# mikroPAD.net
KiCad netlist of a schematic drawn in EAGLE
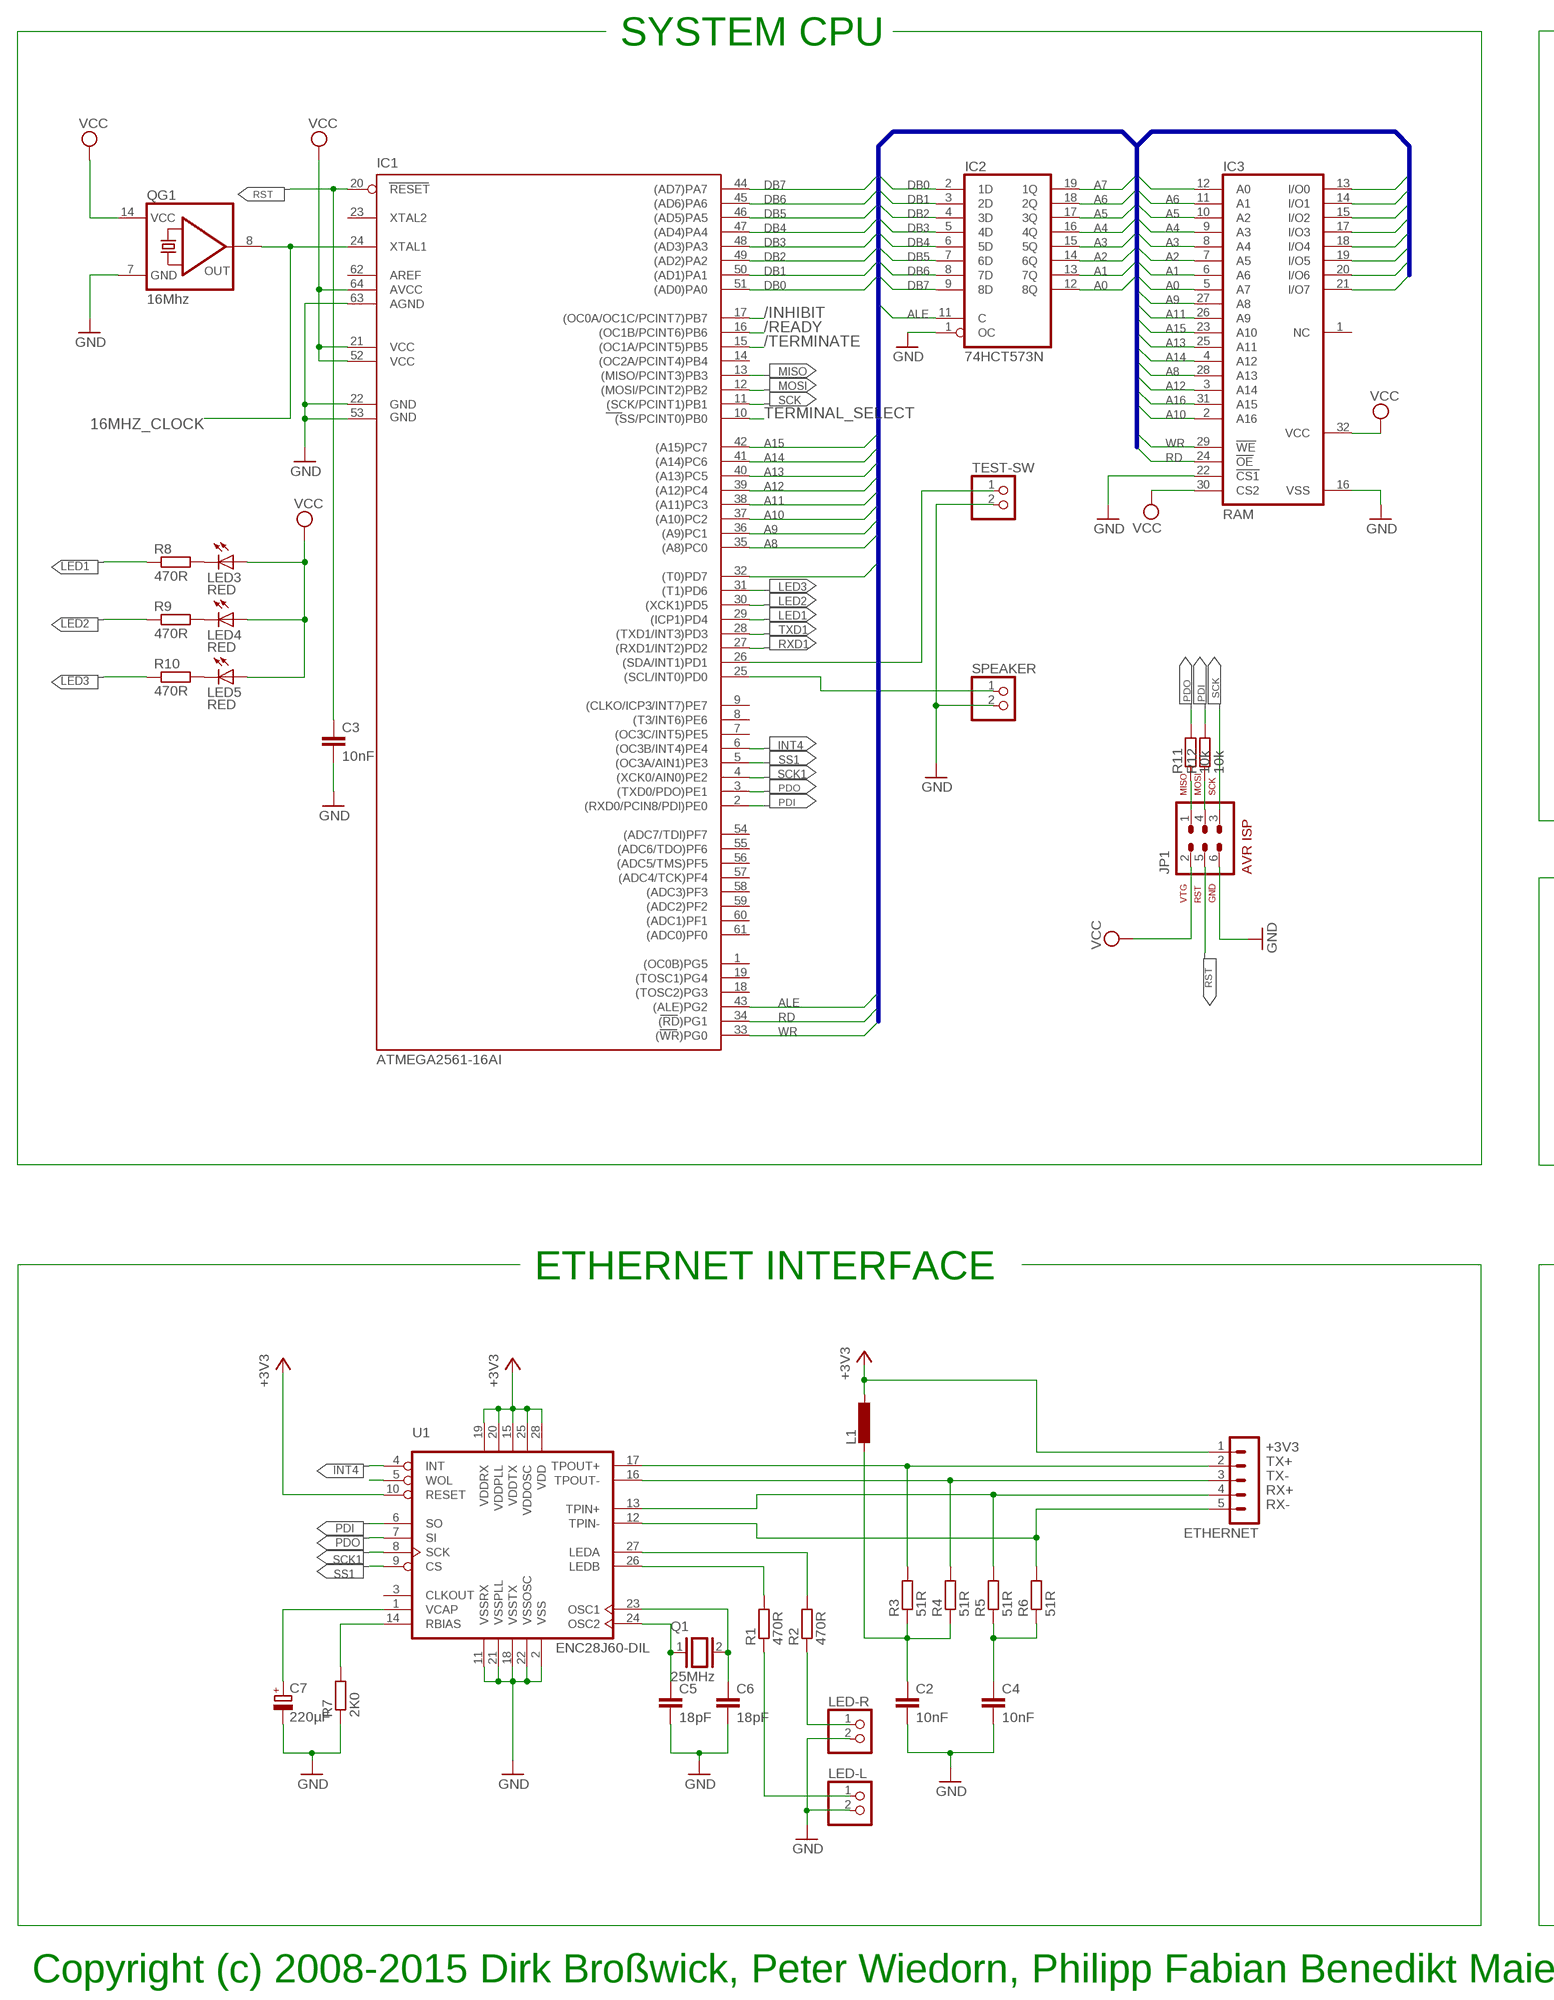
[diagram p0: schematic, sheet 1, part 1 of 2]
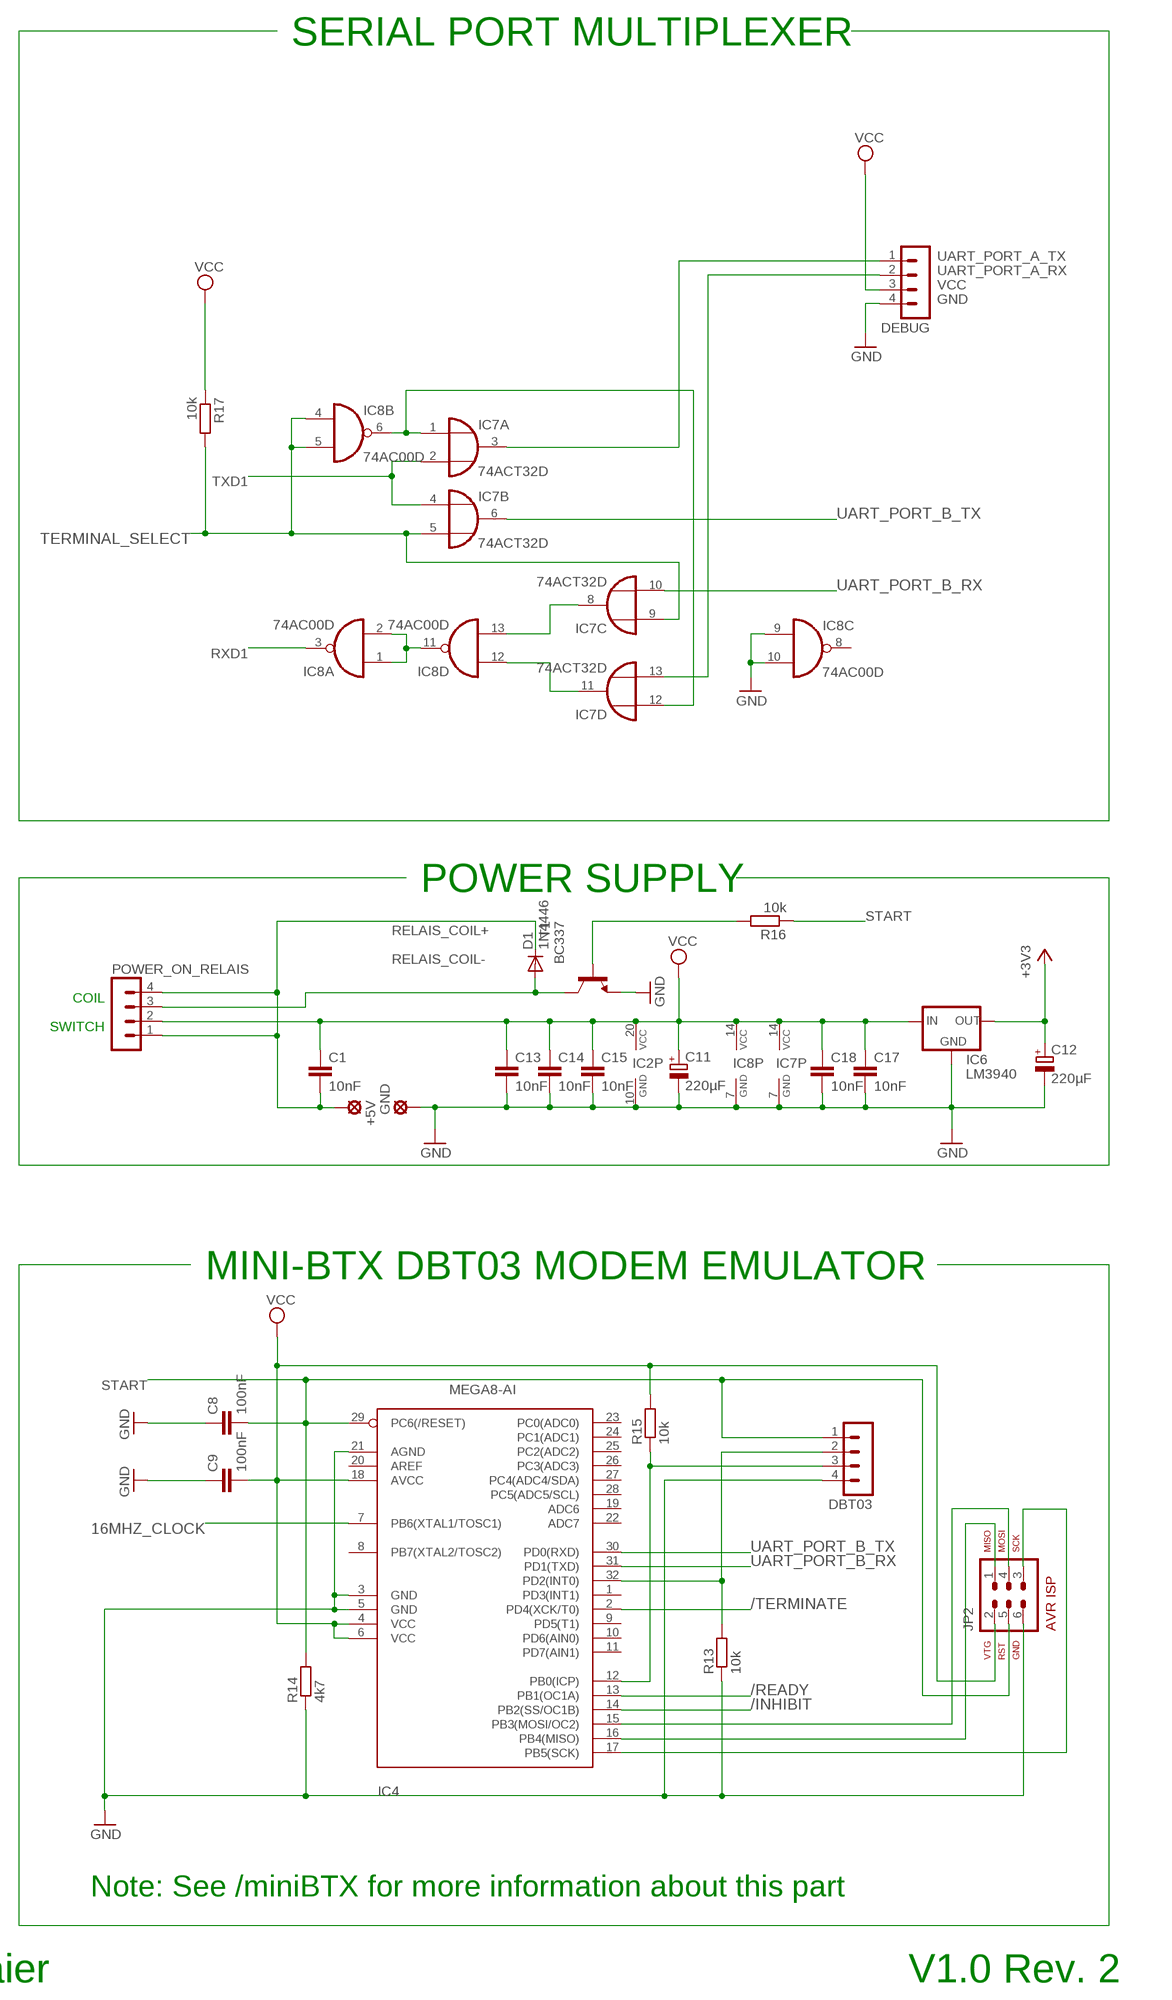
[diagram p1: schematic, sheet 1, part 2 of 2]

(export (version "E")
  (design (tool "Eeschema 10.0.6"))
  (components
    (comp (ref "+5V")
      (value "SE14")
      (footprint "eagle-import:SE14")
      (libsource (lib "eagle-import") (part "SE14"))
    )
    (comp (ref "C1")
      (value "10nF")
      (footprint "eagle-import:C025-025X050")
      (libsource (lib "eagle-import") (part "C-EU025-025X050"))
    )
    (comp (ref "C2")
      (value "10nF")
      (footprint "eagle-import:C025-030X050")
      (libsource (lib "eagle-import") (part "C-EU025-030X050"))
    )
    (comp (ref "C3")
      (value "10nF")
      (footprint "eagle-import:C025-025X050")
      (libsource (lib "eagle-import") (part "C-EU025-025X050"))
    )
    (comp (ref "C4")
      (value "10nF")
      (footprint "eagle-import:C025-030X050")
      (libsource (lib "eagle-import") (part "C-EU025-030X050"))
    )
    (comp (ref "C5")
      (value "18pF")
      (footprint "eagle-import:C025-025X050")
      (libsource (lib "eagle-import") (part "C-EU025-025X050"))
    )
    (comp (ref "C6")
      (value "18pF")
      (footprint "eagle-import:C025-025X050")
      (libsource (lib "eagle-import") (part "C-EU025-025X050"))
    )
    (comp (ref "C7")
      (value "220µF")
      (footprint "eagle-import:E2-5")
      (libsource (lib "eagle-import") (part "CPOL-EUE2-5"))
    )
    (comp (ref "C8")
      (value "100nF")
      (footprint "eagle-import:C025-025X050")
      (libsource (lib "eagle-import") (part "C-EU025-025X050"))
    )
    (comp (ref "C9")
      (value "100nF")
      (footprint "eagle-import:C025-025X050")
      (libsource (lib "eagle-import") (part "C-EU025-025X050"))
    )
    (comp (ref "C11")
      (value "220µF")
      (footprint "eagle-import:E2,5-7")
      (libsource (lib "eagle-import") (part "CPOL-EUE2.5-7"))
    )
    (comp (ref "C12")
      (value "220µF")
      (footprint "eagle-import:E2,5-7")
      (libsource (lib "eagle-import") (part "CPOL-EUE2.5-7"))
    )
    (comp (ref "C13")
      (value "10nF")
      (footprint "eagle-import:C025-025X050")
      (libsource (lib "eagle-import") (part "C-EU025-025X050"))
    )
    (comp (ref "C14")
      (value "10nF")
      (footprint "eagle-import:C025-025X050")
      (libsource (lib "eagle-import") (part "C-EU025-025X050"))
    )
    (comp (ref "C15")
      (value "10nF")
      (footprint "eagle-import:C025-025X050")
      (libsource (lib "eagle-import") (part "C-EU025-025X050"))
    )
    (comp (ref "C17")
      (value "10nF")
      (footprint "eagle-import:C025-025X050")
      (libsource (lib "eagle-import") (part "C-EU025-025X050"))
    )
    (comp (ref "C18")
      (value "10nF")
      (footprint "eagle-import:C025-025X050")
      (libsource (lib "eagle-import") (part "C-EU025-025X050"))
    )
    (comp (ref "D1")
      (value "1N4446")
      (footprint "eagle-import:DO35-10")
      (libsource (lib "eagle-import") (part "1N4446"))
    )
    (comp (ref "DBT03")
      (value "MA04-1")
      (footprint "eagle-import:MA04-1")
      (libsource (lib "eagle-import") (part "MA04-1"))
    )
    (comp (ref "DEBUG")
      (value "MA04-1")
      (footprint "eagle-import:MA04-1")
      (libsource (lib "eagle-import") (part "MA04-1"))
    )
    (comp (ref "ETHERNET")
      (value "MA05-1")
      (footprint "eagle-import:MA05-1")
      (libsource (lib "eagle-import") (part "MA05-1"))
    )
    (comp (ref "GND")
      (value "SE14")
      (footprint "eagle-import:SE14")
      (libsource (lib "eagle-import") (part "SE14"))
    )
    (comp (ref "IC1")
      (value "ATMEGA2561-16AI")
      (footprint "eagle-import:TQFP64")
      (libsource (lib "eagle-import") (part "ATMEGA1281AI-16"))
    )
    (comp (ref "IC2")
      (value "74HCT573N")
      (footprint "eagle-import:DIL20")
      (libsource (lib "eagle-import") (part "74573NHCT"))
    )
    (comp (ref "IC3")
      (value "RAM")
      (footprint "eagle-import:DIL32")
      (libsource (lib "eagle-import") (part "628128P"))
    )
    (comp (ref "IC4")
      (value "MEGA8-AI")
      (footprint "eagle-import:TQFP32-08")
      (libsource (lib "eagle-import") (part "MEGA8-AI"))
    )
    (comp (ref "IC6")
      (value "LM3940")
      (footprint "eagle-import:78XXS")
      (libsource (lib "eagle-import") (part "78XXS"))
    )
    (comp (ref "IC7")
      (value "74ACT32D")
      (footprint "eagle-import:SO14")
      (libsource (lib "eagle-import") (part "7432DACT"))
    )
    (comp (ref "IC8")
      (value "74AC00D")
      (footprint "eagle-import:SO14")
      (libsource (lib "eagle-import") (part "7400DAC"))
    )
    (comp (ref "JP1")
      (value "AVR-ISP-6")
      (footprint "eagle-import:AVR-ISP-6")
      (libsource (lib "eagle-import") (part "AVR-ISP-6"))
    )
    (comp (ref "JP2")
      (value "AVR-ISP-6")
      (footprint "eagle-import:AVR-ISP-6")
      (libsource (lib "eagle-import") (part "AVR-ISP-6"))
    )
    (comp (ref "L1")
      (value "L-EU0207/10")
      (footprint "eagle-import:0207_10")
      (libsource (lib "eagle-import") (part "L-EU0207/10"))
    )
    (comp (ref "LED-L")
      (value "PINHD-1X2")
      (footprint "eagle-import:1X02")
      (libsource (lib "eagle-import") (part "PINHD-1X2"))
    )
    (comp (ref "LED-R")
      (value "PINHD-1X2")
      (footprint "eagle-import:1X02")
      (libsource (lib "eagle-import") (part "PINHD-1X2"))
    )
    (comp (ref "LED3")
      (value "RED")
      (footprint "eagle-import:LED3MM")
      (libsource (lib "eagle-import") (part "LED3MM"))
    )
    (comp (ref "LED4")
      (value "RED")
      (footprint "eagle-import:LED3MM")
      (libsource (lib "eagle-import") (part "LED3MM"))
    )
    (comp (ref "LED5")
      (value "RED")
      (footprint "eagle-import:LED3MM")
      (libsource (lib "eagle-import") (part "LED3MM"))
    )
    (comp (ref "POWER_ON_RELAIS")
      (value "MA04-1")
      (footprint "eagle-import:MA04-1")
      (libsource (lib "eagle-import") (part "MA04-1"))
    )
    (comp (ref "Q1")
      (value "25MHz")
      (footprint "eagle-import:QS")
      (libsource (lib "eagle-import") (part "XTAL/S"))
    )
    (comp (ref "QG1")
      (value "16Mhz")
      (footprint "eagle-import:DIL14S")
      (libsource (lib "eagle-import") (part "QG5860"))
    )
    (comp (ref "R1")
      (value "470R")
      (footprint "eagle-import:0207_10")
      (libsource (lib "eagle-import") (part "R-EU_0207/10"))
    )
    (comp (ref "R2")
      (value "470R")
      (footprint "eagle-import:0207_10")
      (libsource (lib "eagle-import") (part "R-EU_0207/10"))
    )
    (comp (ref "R3")
      (value "51R")
      (footprint "eagle-import:0207_10")
      (libsource (lib "eagle-import") (part "R-EU_0207/10"))
    )
    (comp (ref "R4")
      (value "51R")
      (footprint "eagle-import:0207_10")
      (libsource (lib "eagle-import") (part "R-EU_0207/10"))
    )
    (comp (ref "R5")
      (value "51R")
      (footprint "eagle-import:0207_10")
      (libsource (lib "eagle-import") (part "R-EU_0207/10"))
    )
    (comp (ref "R6")
      (value "51R")
      (footprint "eagle-import:0207_10")
      (libsource (lib "eagle-import") (part "R-EU_0207/10"))
    )
    (comp (ref "R7")
      (value "2K0")
      (footprint "eagle-import:0207_10")
      (libsource (lib "eagle-import") (part "R-EU_0207/10"))
    )
    (comp (ref "R8")
      (value "470R")
      (footprint "eagle-import:0207_10")
      (libsource (lib "eagle-import") (part "R-EU_0207/10"))
    )
    (comp (ref "R9")
      (value "470R")
      (footprint "eagle-import:0207_10")
      (libsource (lib "eagle-import") (part "R-EU_0207/10"))
    )
    (comp (ref "R10")
      (value "470R")
      (footprint "eagle-import:0207_10")
      (libsource (lib "eagle-import") (part "R-EU_0207/10"))
    )
    (comp (ref "R11")
      (value "10k")
      (footprint "eagle-import:0204_5")
      (libsource (lib "eagle-import") (part "R-EU_0204/5"))
    )
    (comp (ref "R12")
      (value "10k")
      (footprint "eagle-import:0204_5")
      (libsource (lib "eagle-import") (part "R-EU_0204/5"))
    )
    (comp (ref "R13")
      (value "10k")
      (footprint "eagle-import:0204_5")
      (libsource (lib "eagle-import") (part "R-EU_0204/5"))
    )
    (comp (ref "R14")
      (value "4k7")
      (footprint "eagle-import:0204_5")
      (libsource (lib "eagle-import") (part "R-EU_0204/5"))
    )
    (comp (ref "R15")
      (value "10k")
      (footprint "eagle-import:0204_5")
      (libsource (lib "eagle-import") (part "R-EU_0204/5"))
    )
    (comp (ref "R16")
      (value "10k")
      (footprint "eagle-import:0207_12")
      (libsource (lib "eagle-import") (part "R-EU_0207/12"))
    )
    (comp (ref "R17")
      (value "10k")
      (footprint "eagle-import:0204_7")
      (libsource (lib "eagle-import") (part "R-EU_0204/7"))
    )
    (comp (ref "SPEAKER")
      (value "PINHD-1X2")
      (footprint "eagle-import:1X02")
      (libsource (lib "eagle-import") (part "PINHD-1X2"))
    )
    (comp (ref "T1")
      (value "BC337")
      (footprint "eagle-import:TO92")
      (libsource (lib "eagle-import") (part "BC337"))
    )
    (comp (ref "TEST-SW")
      (value "PINHD-1X2")
      (footprint "eagle-import:1X02")
      (libsource (lib "eagle-import") (part "PINHD-1X2"))
    )
    (comp (ref "U1")
      (value "ENC28J60-DIL")
      (footprint "eagle-import:DIL28-3")
      (libsource (lib "eagle-import") (part "ENC28J60-DIL"))
    )
  )
  (nets
    (net (code "1") (name "+3V3") (class "Default")
      (node (ref "C12") (pin "+") (pinfunction "+_+") (pintype "passive"))
      (node (ref "ETHERNET") (pin "1") (pinfunction "1_1") (pintype "passive"))
      (node (ref "IC6") (pin "OUT") (pinfunction "OUT_OUT") (pintype "passive"))
      (node (ref "L1") (pin "1") (pinfunction "1_1") (pintype "passive"))
      (node (ref "U1") (pin "10") (pinfunction "RESET_10") (pintype "input"))
      (node (ref "U1") (pin "15") (pinfunction "VDDTX_15") (pintype "power_in"))
      (node (ref "U1") (pin "19") (pinfunction "VDDRX_19") (pintype "power_in"))
      (node (ref "U1") (pin "20") (pinfunction "VDDPLL_20") (pintype "power_in"))
      (node (ref "U1") (pin "25") (pinfunction "VDDOSC_25") (pintype "power_in"))
      (node (ref "U1") (pin "28") (pinfunction "VDD_28") (pintype "power_in"))
    )
    (net (code "2") (name "/16MHZ_CLOCK") (class "Default")
      (node (ref "IC1") (pin "24") (pinfunction "XTAL1_24") (pintype "input"))
      (node (ref "IC4") (pin "7") (pinfunction "PB6(XTAL1/TOSC1)_7") (pintype "bidirectional"))
      (node (ref "QG1") (pin "8") (pinfunction "OUT_8") (pintype "output"))
    )
    (net (code "3") (name "/A0") (class "Default")
      (node (ref "IC2") (pin "12") (pinfunction "8Q_12") (pintype "tri_state"))
      (node (ref "IC3") (pin "5") (pinfunction "A7_5") (pintype "input"))
    )
    (net (code "4") (name "/A1") (class "Default")
      (node (ref "IC2") (pin "13") (pinfunction "7Q_13") (pintype "tri_state"))
      (node (ref "IC3") (pin "6") (pinfunction "A6_6") (pintype "input"))
    )
    (net (code "5") (name "/A2") (class "Default")
      (node (ref "IC2") (pin "14") (pinfunction "6Q_14") (pintype "tri_state"))
      (node (ref "IC3") (pin "7") (pinfunction "A5_7") (pintype "input"))
    )
    (net (code "6") (name "/A3") (class "Default")
      (node (ref "IC2") (pin "15") (pinfunction "5Q_15") (pintype "tri_state"))
      (node (ref "IC3") (pin "8") (pinfunction "A4_8") (pintype "input"))
    )
    (net (code "7") (name "/A4") (class "Default")
      (node (ref "IC2") (pin "16") (pinfunction "4Q_16") (pintype "tri_state"))
      (node (ref "IC3") (pin "9") (pinfunction "A3_9") (pintype "input"))
    )
    (net (code "8") (name "/A5") (class "Default")
      (node (ref "IC2") (pin "17") (pinfunction "3Q_17") (pintype "tri_state"))
      (node (ref "IC3") (pin "10") (pinfunction "A2_10") (pintype "input"))
    )
    (net (code "9") (name "/A6") (class "Default")
      (node (ref "IC2") (pin "18") (pinfunction "2Q_18") (pintype "tri_state"))
      (node (ref "IC3") (pin "11") (pinfunction "A1_11") (pintype "input"))
    )
    (net (code "10") (name "/A7") (class "Default")
      (node (ref "IC2") (pin "19") (pinfunction "1Q_19") (pintype "tri_state"))
      (node (ref "IC3") (pin "12") (pinfunction "A0_12") (pintype "input"))
    )
    (net (code "11") (name "/A8") (class "Default")
      (node (ref "IC1") (pin "35") (pinfunction "(A8)PC0_35") (pintype "bidirectional"))
      (node (ref "IC3") (pin "28") (pinfunction "A13_28") (pintype "input"))
    )
    (net (code "12") (name "/A9") (class "Default")
      (node (ref "IC1") (pin "36") (pinfunction "(A9)PC1_36") (pintype "bidirectional"))
      (node (ref "IC3") (pin "27") (pinfunction "A8_27") (pintype "input"))
    )
    (net (code "13") (name "/A10") (class "Default")
      (node (ref "IC1") (pin "37") (pinfunction "(A10)PC2_37") (pintype "bidirectional"))
      (node (ref "IC3") (pin "2") (pinfunction "A16_2") (pintype "input"))
    )
    (net (code "14") (name "/A11") (class "Default")
      (node (ref "IC1") (pin "38") (pinfunction "(A11)PC3_38") (pintype "bidirectional"))
      (node (ref "IC3") (pin "26") (pinfunction "A9_26") (pintype "input"))
    )
    (net (code "15") (name "/A12") (class "Default")
      (node (ref "IC1") (pin "39") (pinfunction "(A12)PC4_39") (pintype "bidirectional"))
      (node (ref "IC3") (pin "3") (pinfunction "A14_3") (pintype "input"))
    )
    (net (code "16") (name "/A13") (class "Default")
      (node (ref "IC1") (pin "40") (pinfunction "(A13)PC5_40") (pintype "bidirectional"))
      (node (ref "IC3") (pin "25") (pinfunction "A11_25") (pintype "input"))
    )
    (net (code "17") (name "/A14") (class "Default")
      (node (ref "IC1") (pin "41") (pinfunction "(A14)PC6_41") (pintype "bidirectional"))
      (node (ref "IC3") (pin "4") (pinfunction "A12_4") (pintype "input"))
    )
    (net (code "18") (name "/A15") (class "Default")
      (node (ref "IC1") (pin "42") (pinfunction "(A15)PC7_42") (pintype "bidirectional"))
      (node (ref "IC3") (pin "23") (pinfunction "A10_23") (pintype "input"))
    )
    (net (code "19") (name "/A16") (class "Default")
      (node (ref "IC1") (pin "32") (pinfunction "(T0)PD7_32") (pintype "bidirectional"))
      (node (ref "IC3") (pin "31") (pinfunction "A15_31") (pintype "input"))
    )
    (net (code "20") (name "/ALE") (class "Default")
      (node (ref "IC1") (pin "43") (pinfunction "(ALE)PG2_43") (pintype "bidirectional"))
      (node (ref "IC2") (pin "11") (pinfunction "C_11") (pintype "input"))
    )
    (net (code "21") (name "/DB0") (class "Default")
      (node (ref "IC1") (pin "51") (pinfunction "(AD0)PA0_51") (pintype "bidirectional"))
      (node (ref "IC2") (pin "2") (pinfunction "1D_2") (pintype "input"))
      (node (ref "IC3") (pin "15") (pinfunction "I/O2_15") (pintype "bidirectional"))
    )
    (net (code "22") (name "/DB1") (class "Default")
      (node (ref "IC1") (pin "50") (pinfunction "(AD1)PA1_50") (pintype "bidirectional"))
      (node (ref "IC2") (pin "3") (pinfunction "2D_3") (pintype "input"))
      (node (ref "IC3") (pin "14") (pinfunction "I/O1_14") (pintype "bidirectional"))
    )
    (net (code "23") (name "/DB2") (class "Default")
      (node (ref "IC1") (pin "49") (pinfunction "(AD2)PA2_49") (pintype "bidirectional"))
      (node (ref "IC2") (pin "4") (pinfunction "3D_4") (pintype "input"))
      (node (ref "IC3") (pin "13") (pinfunction "I/O0_13") (pintype "bidirectional"))
    )
    (net (code "24") (name "/DB3") (class "Default")
      (node (ref "IC1") (pin "48") (pinfunction "(AD3)PA3_48") (pintype "bidirectional"))
      (node (ref "IC2") (pin "5") (pinfunction "4D_5") (pintype "input"))
      (node (ref "IC3") (pin "17") (pinfunction "I/O3_17") (pintype "bidirectional"))
    )
    (net (code "25") (name "/DB4") (class "Default")
      (node (ref "IC1") (pin "47") (pinfunction "(AD4)PA4_47") (pintype "bidirectional"))
      (node (ref "IC2") (pin "6") (pinfunction "5D_6") (pintype "input"))
      (node (ref "IC3") (pin "18") (pinfunction "I/O4_18") (pintype "bidirectional"))
    )
    (net (code "26") (name "/DB5") (class "Default")
      (node (ref "IC1") (pin "46") (pinfunction "(AD5)PA5_46") (pintype "bidirectional"))
      (node (ref "IC2") (pin "7") (pinfunction "6D_7") (pintype "input"))
      (node (ref "IC3") (pin "19") (pinfunction "I/O5_19") (pintype "bidirectional"))
    )
    (net (code "27") (name "/DB6") (class "Default")
      (node (ref "IC1") (pin "45") (pinfunction "(AD6)PA6_45") (pintype "bidirectional"))
      (node (ref "IC2") (pin "8") (pinfunction "7D_8") (pintype "input"))
      (node (ref "IC3") (pin "20") (pinfunction "I/O6_20") (pintype "bidirectional"))
    )
    (net (code "28") (name "/DB7") (class "Default")
      (node (ref "IC1") (pin "44") (pinfunction "(AD7)PA7_44") (pintype "bidirectional"))
      (node (ref "IC2") (pin "9") (pinfunction "8D_9") (pintype "input"))
      (node (ref "IC3") (pin "21") (pinfunction "I/O7_21") (pintype "bidirectional"))
    )
    (net (code "29") (name "/INT4") (class "Default")
      (node (ref "IC1") (pin "6") (pinfunction "(OC3B/INT4)PE4_6") (pintype "bidirectional"))
      (node (ref "U1") (pin "4") (pinfunction "INT_4") (pintype "output"))
    )
    (net (code "30") (name "/LED1") (class "Default")
      (node (ref "IC1") (pin "29") (pinfunction "(ICP1)PD4_29") (pintype "bidirectional"))
      (node (ref "R8") (pin "1") (pinfunction "1_1") (pintype "passive"))
    )
    (net (code "31") (name "/LED2") (class "Default")
      (node (ref "IC1") (pin "30") (pinfunction "(XCK1)PD5_30") (pintype "bidirectional"))
      (node (ref "R9") (pin "1") (pinfunction "1_1") (pintype "passive"))
    )
    (net (code "32") (name "/LED3") (class "Default")
      (node (ref "IC1") (pin "31") (pinfunction "(T1)PD6_31") (pintype "bidirectional"))
      (node (ref "R10") (pin "1") (pinfunction "1_1") (pintype "passive"))
    )
    (net (code "33") (name "/MISO") (class "Default")
      (node (ref "IC1") (pin "13") (pinfunction "(MISO/PCINT3)PB3_13") (pintype "bidirectional"))
    )
    (net (code "34") (name "/MOSI") (class "Default")
      (node (ref "IC1") (pin "12") (pinfunction "(MOSI/PCINT2)PB2_12") (pintype "bidirectional"))
    )
    (net (code "35") (name "/PDI") (class "Default")
      (node (ref "IC1") (pin "2") (pinfunction "(RXD0/PCIN8/PDI)PE0_2") (pintype "bidirectional"))
      (node (ref "R12") (pin "2") (pinfunction "2_2") (pintype "passive"))
      (node (ref "U1") (pin "6") (pinfunction "SO_6") (pintype "output"))
    )
    (net (code "36") (name "/PDO") (class "Default")
      (node (ref "IC1") (pin "3") (pinfunction "(TXD0/PDO)PE1_3") (pintype "bidirectional"))
      (node (ref "R11") (pin "2") (pinfunction "2_2") (pintype "passive"))
      (node (ref "U1") (pin "7") (pinfunction "SI_7") (pintype "input"))
    )
    (net (code "37") (name "/RD") (class "Default")
      (node (ref "IC1") (pin "34") (pinfunction "(RD)PG1_34") (pintype "bidirectional"))
      (node (ref "IC3") (pin "24") (pinfunction "~{OE}_24") (pintype "input"))
    )
    (net (code "38") (name "/RELAIS_COIL+") (class "Default")
      (node (ref "+5V") (pin "MP") (pinfunction "MP_MP") (pintype "passive"))
      (node (ref "C1") (pin "2") (pinfunction "2_2") (pintype "passive"))
      (node (ref "D1") (pin "C") (pinfunction "C_C") (pintype "passive"))
      (node (ref "POWER_ON_RELAIS") (pin "1") (pinfunction "1_1") (pintype "passive"))
      (node (ref "POWER_ON_RELAIS") (pin "4") (pinfunction "4_4") (pintype "passive"))
    )
    (net (code "39") (name "/RELAIS_COIL-") (class "Default")
      (node (ref "D1") (pin "A") (pinfunction "A_A") (pintype "passive"))
      (node (ref "POWER_ON_RELAIS") (pin "3") (pinfunction "3_3") (pintype "passive"))
      (node (ref "T1") (pin "3") (pinfunction "C_3") (pintype "passive"))
    )
    (net (code "40") (name "/RST") (class "Default")
      (node (ref "C3") (pin "1") (pinfunction "1_1") (pintype "passive"))
      (node (ref "IC1") (pin "20") (pinfunction "RESET_20") (pintype "input"))
      (node (ref "JP1") (pin "5") (pinfunction "5_5") (pintype "passive"))
    )
    (net (code "41") (name "/RX+") (class "Default")
      (node (ref "ETHERNET") (pin "4") (pinfunction "4_4") (pintype "passive"))
      (node (ref "R5") (pin "2") (pinfunction "2_2") (pintype "passive"))
      (node (ref "U1") (pin "13") (pinfunction "TPIN+_13") (pintype "input"))
    )
    (net (code "42") (name "/RX-") (class "Default")
      (node (ref "ETHERNET") (pin "5") (pinfunction "5_5") (pintype "passive"))
      (node (ref "R6") (pin "2") (pinfunction "2_2") (pintype "passive"))
      (node (ref "U1") (pin "12") (pinfunction "TPIN-_12") (pintype "input"))
    )
    (net (code "43") (name "/RXD1") (class "Default")
      (node (ref "IC1") (pin "27") (pinfunction "(RXD1/INT2)PD2_27") (pintype "bidirectional"))
      (node (ref "IC8") (pin "3") (pinfunction "O_3") (pintype "output"))
    )
    (net (code "44") (name "/SCK") (class "Default")
      (node (ref "IC1") (pin "11") (pinfunction "(SCK/PCINT1)PB1_11") (pintype "bidirectional"))
      (node (ref "JP1") (pin "3") (pinfunction "3_3") (pintype "passive"))
    )
    (net (code "45") (name "/SCK1") (class "Default")
      (node (ref "IC1") (pin "4") (pinfunction "(XCK0/AIN0)PE2_4") (pintype "bidirectional"))
      (node (ref "U1") (pin "8") (pinfunction "SCK_8") (pintype "input"))
    )
    (net (code "46") (name "/SS1") (class "Default")
      (node (ref "IC1") (pin "5") (pinfunction "(OC3A/AIN1)PE3_5") (pintype "bidirectional"))
      (node (ref "U1") (pin "9") (pinfunction "CS_9") (pintype "input"))
    )
    (net (code "47") (name "/START") (class "Default")
      (node (ref "C8") (pin "2") (pinfunction "2_2") (pintype "passive"))
      (node (ref "DBT03") (pin "1") (pinfunction "1_1") (pintype "passive"))
      (node (ref "IC4") (pin "29") (pinfunction "PC6(/RESET)_29") (pintype "bidirectional"))
      (node (ref "JP2") (pin "5") (pinfunction "5_5") (pintype "passive"))
      (node (ref "R14") (pin "2") (pinfunction "2_2") (pintype "passive"))
      (node (ref "R16") (pin "1") (pinfunction "1_1") (pintype "passive"))
    )
    (net (code "48") (name "/TERMINAL_SELECT") (class "Default")
      (node (ref "IC1") (pin "10") (pinfunction "(SS/PCINT0)PB0_10") (pintype "bidirectional"))
      (node (ref "IC7") (pin "5") (pinfunction "I1_5") (pintype "input"))
      (node (ref "IC7") (pin "9") (pinfunction "I0_9") (pintype "input"))
      (node (ref "IC8") (pin "4") (pinfunction "I0_4") (pintype "input"))
      (node (ref "IC8") (pin "5") (pinfunction "I1_5") (pintype "input"))
      (node (ref "R17") (pin "2") (pinfunction "2_2") (pintype "passive"))
    )
    (net (code "49") (name "/TX+") (class "Default")
      (node (ref "ETHERNET") (pin "2") (pinfunction "2_2") (pintype "passive"))
      (node (ref "R3") (pin "2") (pinfunction "2_2") (pintype "passive"))
      (node (ref "U1") (pin "17") (pinfunction "TPOUT+_17") (pintype "output"))
    )
    (net (code "50") (name "/TX-") (class "Default")
      (node (ref "ETHERNET") (pin "3") (pinfunction "3_3") (pintype "passive"))
      (node (ref "R4") (pin "2") (pinfunction "2_2") (pintype "passive"))
      (node (ref "U1") (pin "16") (pinfunction "TPOUT-_16") (pintype "output"))
    )
    (net (code "51") (name "/TXD1") (class "Default")
      (node (ref "IC1") (pin "28") (pinfunction "(TXD1/INT3)PD3_28") (pintype "bidirectional"))
      (node (ref "IC7") (pin "2") (pinfunction "I1_2") (pintype "input"))
      (node (ref "IC7") (pin "4") (pinfunction "I0_4") (pintype "input"))
    )
    (net (code "52") (name "/UART_PORT_A_RX") (class "Default")
      (node (ref "DEBUG") (pin "2") (pinfunction "2_2") (pintype "passive"))
      (node (ref "IC7") (pin "13") (pinfunction "I1_13") (pintype "input"))
    )
    (net (code "53") (name "/UART_PORT_A_TX") (class "Default")
      (node (ref "DEBUG") (pin "1") (pinfunction "1_1") (pintype "passive"))
      (node (ref "IC7") (pin "3") (pinfunction "O_3") (pintype "output"))
    )
    (net (code "54") (name "/UART_PORT_B_RX") (class "Default")
      (node (ref "IC4") (pin "31") (pinfunction "PD1(TXD)_31") (pintype "bidirectional"))
      (node (ref "IC7") (pin "10") (pinfunction "I1_10") (pintype "input"))
    )
    (net (code "55") (name "/UART_PORT_B_TX") (class "Default")
      (node (ref "IC4") (pin "30") (pinfunction "PD0(RXD)_30") (pintype "bidirectional"))
      (node (ref "IC7") (pin "6") (pinfunction "O_6") (pintype "output"))
    )
    (net (code "56") (name "/WR") (class "Default")
      (node (ref "IC1") (pin "33") (pinfunction "(WR)PG0_33") (pintype "bidirectional"))
      (node (ref "IC3") (pin "29") (pinfunction "~{WE}_29") (pintype "input"))
    )
    (net (code "57") (name "/{slash}INHIBIT") (class "Default")
      (node (ref "IC1") (pin "17") (pinfunction "(OC0A/OC1C/PCINT7)PB7_17") (pintype "bidirectional"))
      (node (ref "IC4") (pin "14") (pinfunction "PB2(SS/OC1B)_14") (pintype "bidirectional"))
    )
    (net (code "58") (name "/{slash}READY") (class "Default")
      (node (ref "IC1") (pin "16") (pinfunction "(OC1B/PCINT6)PB6_16") (pintype "bidirectional"))
      (node (ref "IC4") (pin "13") (pinfunction "PB1(OC1A)_13") (pintype "bidirectional"))
    )
    (net (code "59") (name "/{slash}TERMINATE") (class "Default")
      (node (ref "IC1") (pin "15") (pinfunction "(OC1A/PCINT5)PB5_15") (pintype "bidirectional"))
      (node (ref "IC4") (pin "2") (pinfunction "PD4(XCK/T0)_2") (pintype "bidirectional"))
    )
    (net (code "60") (name "GND") (class "Default")
      (node (ref "C11") (pin "-") (pinfunction "-_-") (pintype "passive"))
      (node (ref "C12") (pin "-") (pinfunction "-_-") (pintype "passive"))
      (node (ref "C13") (pin "2") (pinfunction "2_2") (pintype "passive"))
      (node (ref "C14") (pin "2") (pinfunction "2_2") (pintype "passive"))
      (node (ref "C15") (pin "2") (pinfunction "2_2") (pintype "passive"))
      (node (ref "C17") (pin "2") (pinfunction "2_2") (pintype "passive"))
      (node (ref "C18") (pin "2") (pinfunction "2_2") (pintype "passive"))
      (node (ref "C2") (pin "2") (pinfunction "2_2") (pintype "passive"))
      (node (ref "C3") (pin "2") (pinfunction "2_2") (pintype "passive"))
      (node (ref "C4") (pin "2") (pinfunction "2_2") (pintype "passive"))
      (node (ref "C5") (pin "2") (pinfunction "2_2") (pintype "passive"))
      (node (ref "C6") (pin "2") (pinfunction "2_2") (pintype "passive"))
      (node (ref "C7") (pin "-") (pinfunction "-_-") (pintype "passive"))
      (node (ref "C8") (pin "1") (pinfunction "1_1") (pintype "passive"))
      (node (ref "C9") (pin "1") (pinfunction "1_1") (pintype "passive"))
      (node (ref "DBT03") (pin "4") (pinfunction "4_4") (pintype "passive"))
      (node (ref "DEBUG") (pin "4") (pinfunction "4_4") (pintype "passive"))
      (node (ref "GND") (pin "MP") (pinfunction "MP_MP") (pintype "passive"))
      (node (ref "IC1") (pin "22") (pinfunction "GND_22") (pintype "power_in"))
      (node (ref "IC1") (pin "53") (pinfunction "GND1_53") (pintype "power_in"))
      (node (ref "IC1") (pin "63") (pinfunction "AGND_63") (pintype "power_in"))
      (node (ref "IC2") (pin "1") (pinfunction "OC_1") (pintype "input"))
      (node (ref "IC2") (pin "10") (pinfunction "GND_10") (pintype "power_in"))
      (node (ref "IC3") (pin "16") (pinfunction "VSS_16") (pintype "power_in"))
      (node (ref "IC3") (pin "22") (pinfunction "~{CS1}_22") (pintype "input"))
      (node (ref "IC4") (pin "21") (pinfunction "AGND_21") (pintype "power_in"))
      (node (ref "IC4") (pin "3") (pinfunction "GND_3") (pintype "power_in"))
      (node (ref "IC4") (pin "5") (pinfunction "GND_5") (pintype "power_in"))
      (node (ref "IC6") (pin "GND") (pinfunction "GND_GND") (pintype "input"))
      (node (ref "IC7") (pin "7") (pinfunction "GND_7") (pintype "power_in"))
      (node (ref "IC8") (pin "10") (pinfunction "I1_10") (pintype "input"))
      (node (ref "IC8") (pin "7") (pinfunction "GND_7") (pintype "power_in"))
      (node (ref "IC8") (pin "9") (pinfunction "I0_9") (pintype "input"))
      (node (ref "JP1") (pin "6") (pinfunction "6_6") (pintype "passive"))
      (node (ref "JP2") (pin "6") (pinfunction "6_6") (pintype "passive"))
      (node (ref "LED-L") (pin "2") (pinfunction "2_2") (pintype "passive"))
      (node (ref "LED-R") (pin "2") (pinfunction "2_2") (pintype "passive"))
      (node (ref "QG1") (pin "7") (pinfunction "GND_7") (pintype "power_in"))
      (node (ref "R13") (pin "1") (pinfunction "1_1") (pintype "passive"))
      (node (ref "R14") (pin "1") (pinfunction "1_1") (pintype "passive"))
      (node (ref "R7") (pin "1") (pinfunction "1_1") (pintype "passive"))
      (node (ref "SPEAKER") (pin "2") (pinfunction "2_2") (pintype "passive"))
      (node (ref "T1") (pin "1") (pinfunction "E_1") (pintype "passive"))
      (node (ref "TEST-SW") (pin "2") (pinfunction "2_2") (pintype "passive"))
      (node (ref "U1") (pin "11") (pinfunction "VSSRX_11") (pintype "power_in"))
      (node (ref "U1") (pin "18") (pinfunction "VSSTX_18") (pintype "power_in"))
      (node (ref "U1") (pin "2") (pinfunction "VSS_2") (pintype "power_in"))
      (node (ref "U1") (pin "21") (pinfunction "VSSPLL_21") (pintype "power_in"))
      (node (ref "U1") (pin "22") (pinfunction "VSSOSC_22") (pintype "power_in"))
    )
    (net (code "61") (name "Net-(C2-Pad1)") (class "Default")
      (node (ref "C2") (pin "1") (pinfunction "1_1") (pintype "passive"))
      (node (ref "L1") (pin "2") (pinfunction "2_2") (pintype "passive"))
      (node (ref "R3") (pin "1") (pinfunction "1_1") (pintype "passive"))
      (node (ref "R4") (pin "1") (pinfunction "1_1") (pintype "passive"))
    )
    (net (code "62") (name "Net-(C4-Pad1)") (class "Default")
      (node (ref "C4") (pin "1") (pinfunction "1_1") (pintype "passive"))
      (node (ref "R5") (pin "1") (pinfunction "1_1") (pintype "passive"))
      (node (ref "R6") (pin "1") (pinfunction "1_1") (pintype "passive"))
    )
    (net (code "63") (name "Net-(IC1-(SCL{slash}INT0)PD0)") (class "Default")
      (node (ref "IC1") (pin "25") (pinfunction "(SCL/INT0)PD0_25") (pintype "bidirectional"))
      (node (ref "SPEAKER") (pin "1") (pinfunction "1_1") (pintype "passive"))
    )
    (net (code "64") (name "Net-(IC1-(SDA{slash}INT1)PD1)") (class "Default")
      (node (ref "IC1") (pin "26") (pinfunction "(SDA/INT1)PD1_26") (pintype "bidirectional"))
      (node (ref "TEST-SW") (pin "1") (pinfunction "1_1") (pintype "passive"))
    )
    (net (code "65") (name "Net-(IC4-PB0(ICP))") (class "Default")
      (node (ref "DBT03") (pin "3") (pinfunction "3_3") (pintype "passive"))
      (node (ref "IC4") (pin "12") (pinfunction "PB0(ICP)_12") (pintype "bidirectional"))
      (node (ref "R15") (pin "1") (pinfunction "1_1") (pintype "passive"))
    )
    (net (code "66") (name "Net-(IC4-PB3(MOSI{slash}OC2))") (class "Default")
      (node (ref "IC4") (pin "15") (pinfunction "PB3(MOSI/OC2)_15") (pintype "bidirectional"))
      (node (ref "JP2") (pin "4") (pinfunction "4_4") (pintype "passive"))
    )
    (net (code "67") (name "Net-(IC4-PB4(MISO))") (class "Default")
      (node (ref "IC4") (pin "16") (pinfunction "PB4(MISO)_16") (pintype "bidirectional"))
      (node (ref "JP2") (pin "1") (pinfunction "1_1") (pintype "passive"))
    )
    (net (code "68") (name "Net-(IC4-PB5(SCK))") (class "Default")
      (node (ref "IC4") (pin "17") (pinfunction "PB5(SCK)_17") (pintype "bidirectional"))
      (node (ref "JP2") (pin "3") (pinfunction "3_3") (pintype "passive"))
    )
    (net (code "69") (name "Net-(IC4-PD2(INT0))") (class "Default")
      (node (ref "DBT03") (pin "2") (pinfunction "2_2") (pintype "passive"))
      (node (ref "IC4") (pin "32") (pinfunction "PD2(INT0)_32") (pintype "bidirectional"))
      (node (ref "R13") (pin "2") (pinfunction "2_2") (pintype "passive"))
    )
    (net (code "70") (name "Net-(IC7A-I0)") (class "Default")
      (node (ref "IC7") (pin "1") (pinfunction "I0_1") (pintype "input"))
      (node (ref "IC7") (pin "12") (pinfunction "I0_12") (pintype "input"))
      (node (ref "IC8") (pin "6") (pinfunction "O_6") (pintype "output"))
    )
    (net (code "71") (name "Net-(IC7C-O)") (class "Default")
      (node (ref "IC7") (pin "8") (pinfunction "O_8") (pintype "output"))
      (node (ref "IC8") (pin "13") (pinfunction "I1_13") (pintype "input"))
    )
    (net (code "72") (name "Net-(IC7D-O)") (class "Default")
      (node (ref "IC7") (pin "11") (pinfunction "O_11") (pintype "output"))
      (node (ref "IC8") (pin "12") (pinfunction "I0_12") (pintype "input"))
    )
    (net (code "73") (name "Net-(IC8A-I0)") (class "Default")
      (node (ref "IC8") (pin "1") (pinfunction "I0_1") (pintype "input"))
      (node (ref "IC8") (pin "11") (pinfunction "O_11") (pintype "output"))
      (node (ref "IC8") (pin "2") (pinfunction "I1_2") (pintype "input"))
    )
    (net (code "74") (name "Net-(JP1-Pad1)") (class "Default")
      (node (ref "JP1") (pin "1") (pinfunction "1_1") (pintype "passive"))
      (node (ref "R11") (pin "1") (pinfunction "1_1") (pintype "passive"))
    )
    (net (code "75") (name "Net-(JP1-Pad4)") (class "Default")
      (node (ref "JP1") (pin "4") (pinfunction "4_4") (pintype "passive"))
      (node (ref "R12") (pin "1") (pinfunction "1_1") (pintype "passive"))
    )
    (net (code "76") (name "Net-(LED-L-Pad1)") (class "Default")
      (node (ref "LED-L") (pin "1") (pinfunction "1_1") (pintype "passive"))
      (node (ref "R1") (pin "1") (pinfunction "1_1") (pintype "passive"))
    )
    (net (code "77") (name "Net-(LED-R-Pad1)") (class "Default")
      (node (ref "LED-R") (pin "1") (pinfunction "1_1") (pintype "passive"))
      (node (ref "R2") (pin "1") (pinfunction "1_1") (pintype "passive"))
    )
    (net (code "78") (name "Net-(LED3-C)") (class "Default")
      (node (ref "LED3") (pin "K") (pinfunction "C_K") (pintype "passive"))
      (node (ref "R8") (pin "2") (pinfunction "2_2") (pintype "passive"))
    )
    (net (code "79") (name "Net-(LED4-C)") (class "Default")
      (node (ref "LED4") (pin "K") (pinfunction "C_K") (pintype "passive"))
      (node (ref "R9") (pin "2") (pinfunction "2_2") (pintype "passive"))
    )
    (net (code "80") (name "Net-(LED5-C)") (class "Default")
      (node (ref "LED5") (pin "K") (pinfunction "C_K") (pintype "passive"))
      (node (ref "R10") (pin "2") (pinfunction "2_2") (pintype "passive"))
    )
    (net (code "81") (name "Net-(T1-B)") (class "Default")
      (node (ref "R16") (pin "2") (pinfunction "2_2") (pintype "passive"))
      (node (ref "T1") (pin "2") (pinfunction "B_2") (pintype "passive"))
    )
    (net (code "82") (name "Net-(U1-LEDA)") (class "Default")
      (node (ref "R2") (pin "2") (pinfunction "2_2") (pintype "passive"))
      (node (ref "U1") (pin "27") (pinfunction "LEDA_27") (pintype "output"))
    )
    (net (code "83") (name "Net-(U1-LEDB)") (class "Default")
      (node (ref "R1") (pin "2") (pinfunction "2_2") (pintype "passive"))
      (node (ref "U1") (pin "26") (pinfunction "LEDB_26") (pintype "output"))
    )
    (net (code "84") (name "Net-(U1-OSC1)") (class "Default")
      (node (ref "C6") (pin "1") (pinfunction "1_1") (pintype "passive"))
      (node (ref "Q1") (pin "2") (pinfunction "2_2") (pintype "passive"))
      (node (ref "U1") (pin "23") (pinfunction "OSC1_23") (pintype "input"))
    )
    (net (code "85") (name "Net-(U1-OSC2)") (class "Default")
      (node (ref "C5") (pin "1") (pinfunction "1_1") (pintype "passive"))
      (node (ref "Q1") (pin "1") (pinfunction "1_1") (pintype "passive"))
      (node (ref "U1") (pin "24") (pinfunction "OSC2_24") (pintype "output"))
    )
    (net (code "86") (name "Net-(U1-RBIAS)") (class "Default")
      (node (ref "R7") (pin "2") (pinfunction "2_2") (pintype "passive"))
      (node (ref "U1") (pin "14") (pinfunction "RBIAS_14") (pintype "passive"))
    )
    (net (code "87") (name "Net-(U1-VCAP)") (class "Default")
      (node (ref "C7") (pin "+") (pinfunction "+_+") (pintype "passive"))
      (node (ref "U1") (pin "1") (pinfunction "VCAP_1") (pintype "power_in"))
    )
    (net (code "88") (name "VCC") (class "Default")
      (node (ref "C1") (pin "1") (pinfunction "1_1") (pintype "passive"))
      (node (ref "C11") (pin "+") (pinfunction "+_+") (pintype "passive"))
      (node (ref "C13") (pin "1") (pinfunction "1_1") (pintype "passive"))
      (node (ref "C14") (pin "1") (pinfunction "1_1") (pintype "passive"))
      (node (ref "C15") (pin "1") (pinfunction "1_1") (pintype "passive"))
      (node (ref "C17") (pin "1") (pinfunction "1_1") (pintype "passive"))
      (node (ref "C18") (pin "1") (pinfunction "1_1") (pintype "passive"))
      (node (ref "C9") (pin "2") (pinfunction "2_2") (pintype "passive"))
      (node (ref "DEBUG") (pin "3") (pinfunction "3_3") (pintype "passive"))
      (node (ref "IC1") (pin "21") (pinfunction "VCC_21") (pintype "power_in"))
      (node (ref "IC1") (pin "52") (pinfunction "VCC1_52") (pintype "power_in"))
      (node (ref "IC1") (pin "64") (pinfunction "AVCC_64") (pintype "power_in"))
      (node (ref "IC2") (pin "20") (pinfunction "VCC_20") (pintype "power_in"))
      (node (ref "IC3") (pin "30") (pinfunction "CS2_30") (pintype "input"))
      (node (ref "IC3") (pin "32") (pinfunction "VCC_32") (pintype "power_in"))
      (node (ref "IC4") (pin "18") (pinfunction "AVCC_18") (pintype "power_in"))
      (node (ref "IC4") (pin "4") (pinfunction "VCC_4") (pintype "power_in"))
      (node (ref "IC4") (pin "6") (pinfunction "VCC_6") (pintype "power_in"))
      (node (ref "IC6") (pin "IN") (pinfunction "IN_IN") (pintype "input"))
      (node (ref "IC7") (pin "14") (pinfunction "VCC_14") (pintype "power_in"))
      (node (ref "IC8") (pin "14") (pinfunction "VCC_14") (pintype "power_in"))
      (node (ref "JP1") (pin "2") (pinfunction "2_2") (pintype "passive"))
      (node (ref "JP2") (pin "2") (pinfunction "2_2") (pintype "passive"))
      (node (ref "LED3") (pin "A") (pinfunction "A_A") (pintype "passive"))
      (node (ref "LED4") (pin "A") (pinfunction "A_A") (pintype "passive"))
      (node (ref "LED5") (pin "A") (pinfunction "A_A") (pintype "passive"))
      (node (ref "POWER_ON_RELAIS") (pin "2") (pinfunction "2_2") (pintype "passive"))
      (node (ref "QG1") (pin "14") (pinfunction "VCC_14") (pintype "power_in"))
      (node (ref "R15") (pin "2") (pinfunction "2_2") (pintype "passive"))
      (node (ref "R17") (pin "1") (pinfunction "1_1") (pintype "passive"))
    )
    (net (code "89") (name "unconnected-(IC1-(ADC0)PF0-Pad61)") (class "Default")
      (node (ref "IC1") (pin "61") (pinfunction "(ADC0)PF0_61") (pintype "bidirectional"))
    )
    (net (code "90") (name "unconnected-(IC1-(ADC1)PF1-Pad60)") (class "Default")
      (node (ref "IC1") (pin "60") (pinfunction "(ADC1)PF1_60") (pintype "bidirectional"))
    )
    (net (code "91") (name "unconnected-(IC1-(ADC2)PF2-Pad59)") (class "Default")
      (node (ref "IC1") (pin "59") (pinfunction "(ADC2)PF2_59") (pintype "bidirectional"))
    )
    (net (code "92") (name "unconnected-(IC1-(ADC3)PF3-Pad58)") (class "Default")
      (node (ref "IC1") (pin "58") (pinfunction "(ADC3)PF3_58") (pintype "bidirectional"))
    )
    (net (code "93") (name "unconnected-(IC1-(ADC4{slash}TCK)PF4-Pad57)") (class "Default")
      (node (ref "IC1") (pin "57") (pinfunction "(ADC4/TCK)PF4_57") (pintype "bidirectional"))
    )
    (net (code "94") (name "unconnected-(IC1-(ADC5{slash}TMS)PF5-Pad56)") (class "Default")
      (node (ref "IC1") (pin "56") (pinfunction "(ADC5/TMS)PF5_56") (pintype "bidirectional"))
    )
    (net (code "95") (name "unconnected-(IC1-(ADC6{slash}TDO)PF6-Pad55)") (class "Default")
      (node (ref "IC1") (pin "55") (pinfunction "(ADC6/TDO)PF6_55") (pintype "bidirectional"))
    )
    (net (code "96") (name "unconnected-(IC1-(ADC7{slash}TDI)PF7-Pad54)") (class "Default")
      (node (ref "IC1") (pin "54") (pinfunction "(ADC7/TDI)PF7_54") (pintype "bidirectional"))
    )
    (net (code "97") (name "unconnected-(IC1-(CLKO{slash}ICP3{slash}INT7)PE7-Pad9)") (class "Default")
      (node (ref "IC1") (pin "9") (pinfunction "(CLKO/ICP3/INT7)PE7_9") (pintype "bidirectional"))
    )
    (net (code "98") (name "unconnected-(IC1-(OC0B)PG5-Pad1)") (class "Default")
      (node (ref "IC1") (pin "1") (pinfunction "(OC0B)PG5_1") (pintype "bidirectional"))
    )
    (net (code "99") (name "unconnected-(IC1-(OC2A{slash}PCINT4)PB4-Pad14)") (class "Default")
      (node (ref "IC1") (pin "14") (pinfunction "(OC2A/PCINT4)PB4_14") (pintype "bidirectional"))
    )
    (net (code "100") (name "unconnected-(IC1-(OC3C{slash}INT5)PE5-Pad7)") (class "Default")
      (node (ref "IC1") (pin "7") (pinfunction "(OC3C/INT5)PE5_7") (pintype "bidirectional"))
    )
    (net (code "101") (name "unconnected-(IC1-(T3{slash}INT6)PE6-Pad8)") (class "Default")
      (node (ref "IC1") (pin "8") (pinfunction "(T3/INT6)PE6_8") (pintype "bidirectional"))
    )
    (net (code "102") (name "unconnected-(IC1-(TOSC1)PG4-Pad19)") (class "Default")
      (node (ref "IC1") (pin "19") (pinfunction "(TOSC1)PG4_19") (pintype "bidirectional"))
    )
    (net (code "103") (name "unconnected-(IC1-(TOSC2)PG3-Pad18)") (class "Default")
      (node (ref "IC1") (pin "18") (pinfunction "(TOSC2)PG3_18") (pintype "bidirectional"))
    )
    (net (code "104") (name "unconnected-(IC1-AREF-Pad62)") (class "Default")
      (node (ref "IC1") (pin "62") (pinfunction "AREF_62") (pintype "bidirectional"))
    )
    (net (code "105") (name "unconnected-(IC1-XTAL2-Pad23)") (class "Default")
      (node (ref "IC1") (pin "23") (pinfunction "XTAL2_23") (pintype "output"))
    )
    (net (code "106") (name "unconnected-(IC3-NC-Pad1)") (class "Default")
      (node (ref "IC3") (pin "1") (pinfunction "NC_1") (pintype "no_connect"))
    )
    (net (code "107") (name "unconnected-(IC4-ADC6-Pad19)") (class "Default")
      (node (ref "IC4") (pin "19") (pinfunction "ADC6_19") (pintype "bidirectional"))
    )
    (net (code "108") (name "unconnected-(IC4-ADC7-Pad22)") (class "Default")
      (node (ref "IC4") (pin "22") (pinfunction "ADC7_22") (pintype "bidirectional"))
    )
    (net (code "109") (name "unconnected-(IC4-AREF-Pad20)") (class "Default")
      (node (ref "IC4") (pin "20") (pinfunction "AREF_20") (pintype "passive"))
    )
    (net (code "110") (name "unconnected-(IC4-PB7(XTAL2{slash}TOSC2)-Pad8)") (class "Default")
      (node (ref "IC4") (pin "8") (pinfunction "PB7(XTAL2/TOSC2)_8") (pintype "bidirectional"))
    )
    (net (code "111") (name "unconnected-(IC4-PC0(ADC0)-Pad23)") (class "Default")
      (node (ref "IC4") (pin "23") (pinfunction "PC0(ADC0)_23") (pintype "bidirectional"))
    )
    (net (code "112") (name "unconnected-(IC4-PC1(ADC1)-Pad24)") (class "Default")
      (node (ref "IC4") (pin "24") (pinfunction "PC1(ADC1)_24") (pintype "bidirectional"))
    )
    (net (code "113") (name "unconnected-(IC4-PC2(ADC2)-Pad25)") (class "Default")
      (node (ref "IC4") (pin "25") (pinfunction "PC2(ADC2)_25") (pintype "bidirectional"))
    )
    (net (code "114") (name "unconnected-(IC4-PC3(ADC3)-Pad26)") (class "Default")
      (node (ref "IC4") (pin "26") (pinfunction "PC3(ADC3)_26") (pintype "bidirectional"))
    )
    (net (code "115") (name "unconnected-(IC4-PC4(ADC4{slash}SDA)-Pad27)") (class "Default")
      (node (ref "IC4") (pin "27") (pinfunction "PC4(ADC4/SDA)_27") (pintype "bidirectional"))
    )
    (net (code "116") (name "unconnected-(IC4-PC5(ADC5{slash}SCL)-Pad28)") (class "Default")
      (node (ref "IC4") (pin "28") (pinfunction "PC5(ADC5/SCL)_28") (pintype "bidirectional"))
    )
    (net (code "117") (name "unconnected-(IC4-PD3(INT1)-Pad1)") (class "Default")
      (node (ref "IC4") (pin "1") (pinfunction "PD3(INT1)_1") (pintype "bidirectional"))
    )
    (net (code "118") (name "unconnected-(IC4-PD5(T1)-Pad9)") (class "Default")
      (node (ref "IC4") (pin "9") (pinfunction "PD5(T1)_9") (pintype "bidirectional"))
    )
    (net (code "119") (name "unconnected-(IC4-PD6(AIN0)-Pad10)") (class "Default")
      (node (ref "IC4") (pin "10") (pinfunction "PD6(AIN0)_10") (pintype "bidirectional"))
    )
    (net (code "120") (name "unconnected-(IC4-PD7(AIN1)-Pad11)") (class "Default")
      (node (ref "IC4") (pin "11") (pinfunction "PD7(AIN1)_11") (pintype "bidirectional"))
    )
    (net (code "121") (name "unconnected-(IC8C-O-Pad8)") (class "Default")
      (node (ref "IC8") (pin "8") (pinfunction "O_8") (pintype "output"))
    )
    (net (code "122") (name "unconnected-(U1-CLKOUT-Pad3)") (class "Default")
      (node (ref "U1") (pin "3") (pinfunction "CLKOUT_3") (pintype "output"))
    )
    (net (code "123") (name "unconnected-(U1-WOL-Pad5)") (class "Default")
      (node (ref "U1") (pin "5") (pinfunction "WOL_5") (pintype "output"))
    )
  )
)
